# CANBUS_USB.net
KiCad netlist of a schematic drawn in EAGLE
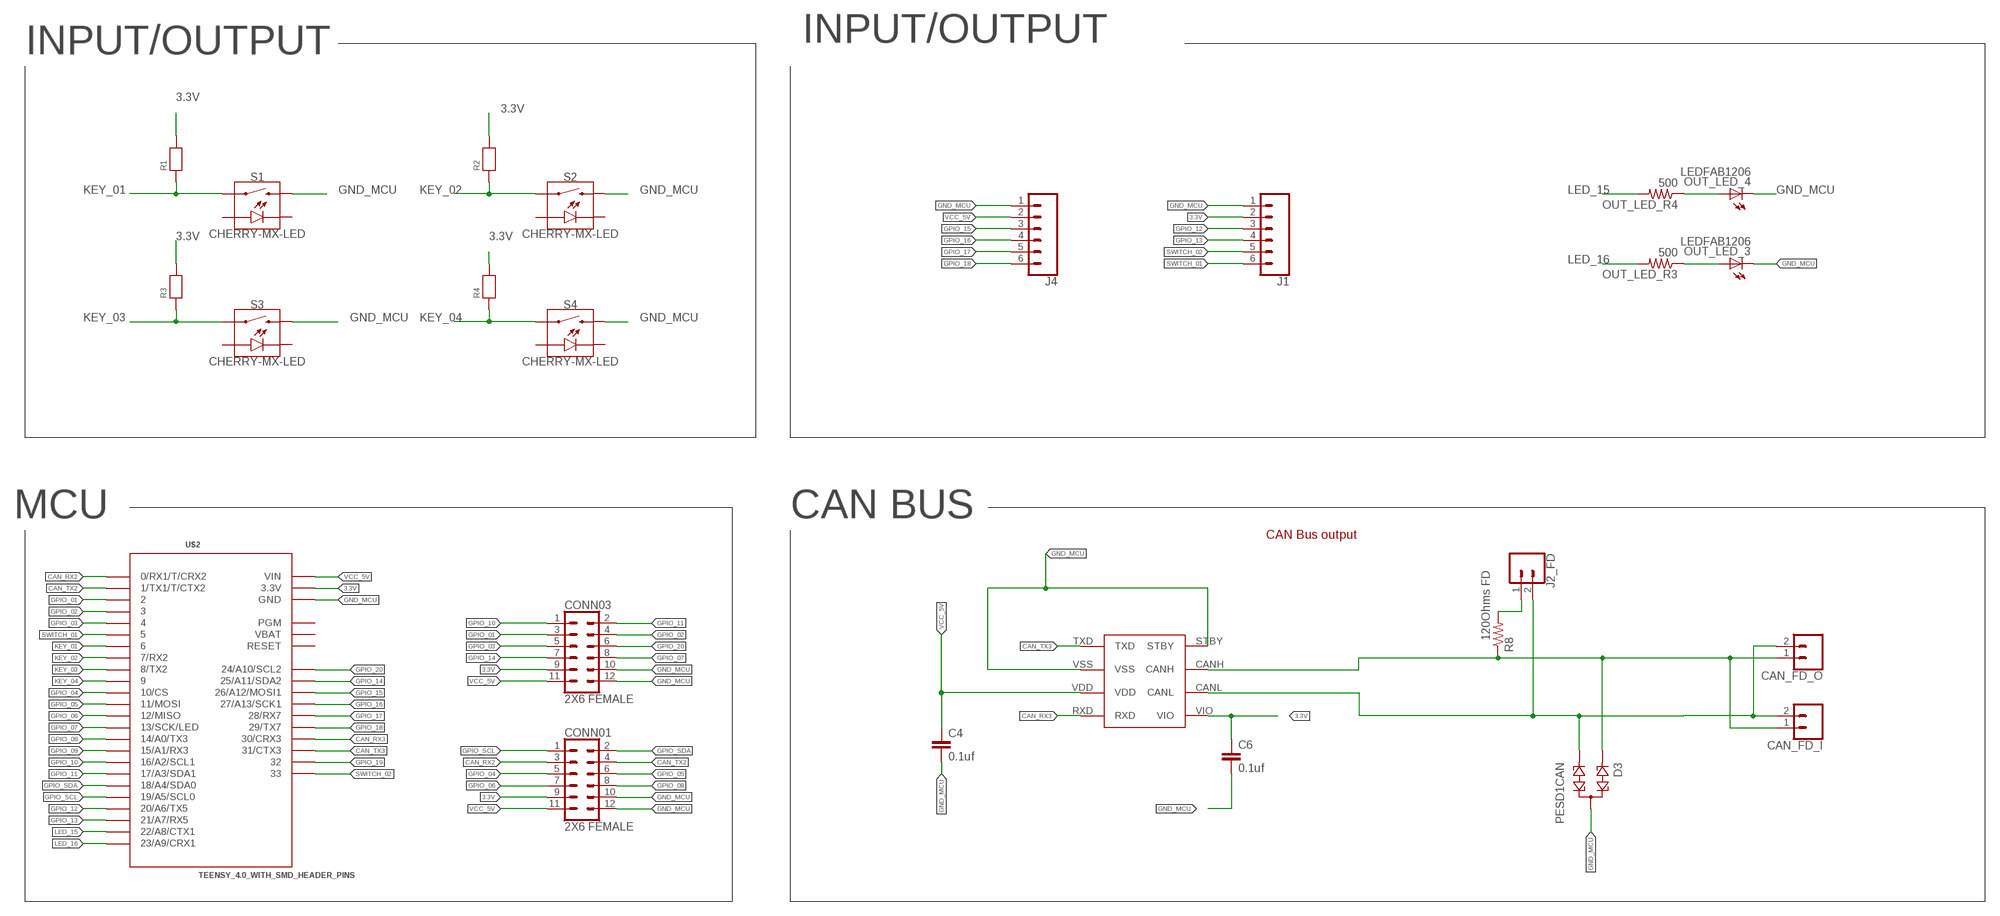
[diagram p0: schematic, sheet 1, part 1 of 2]
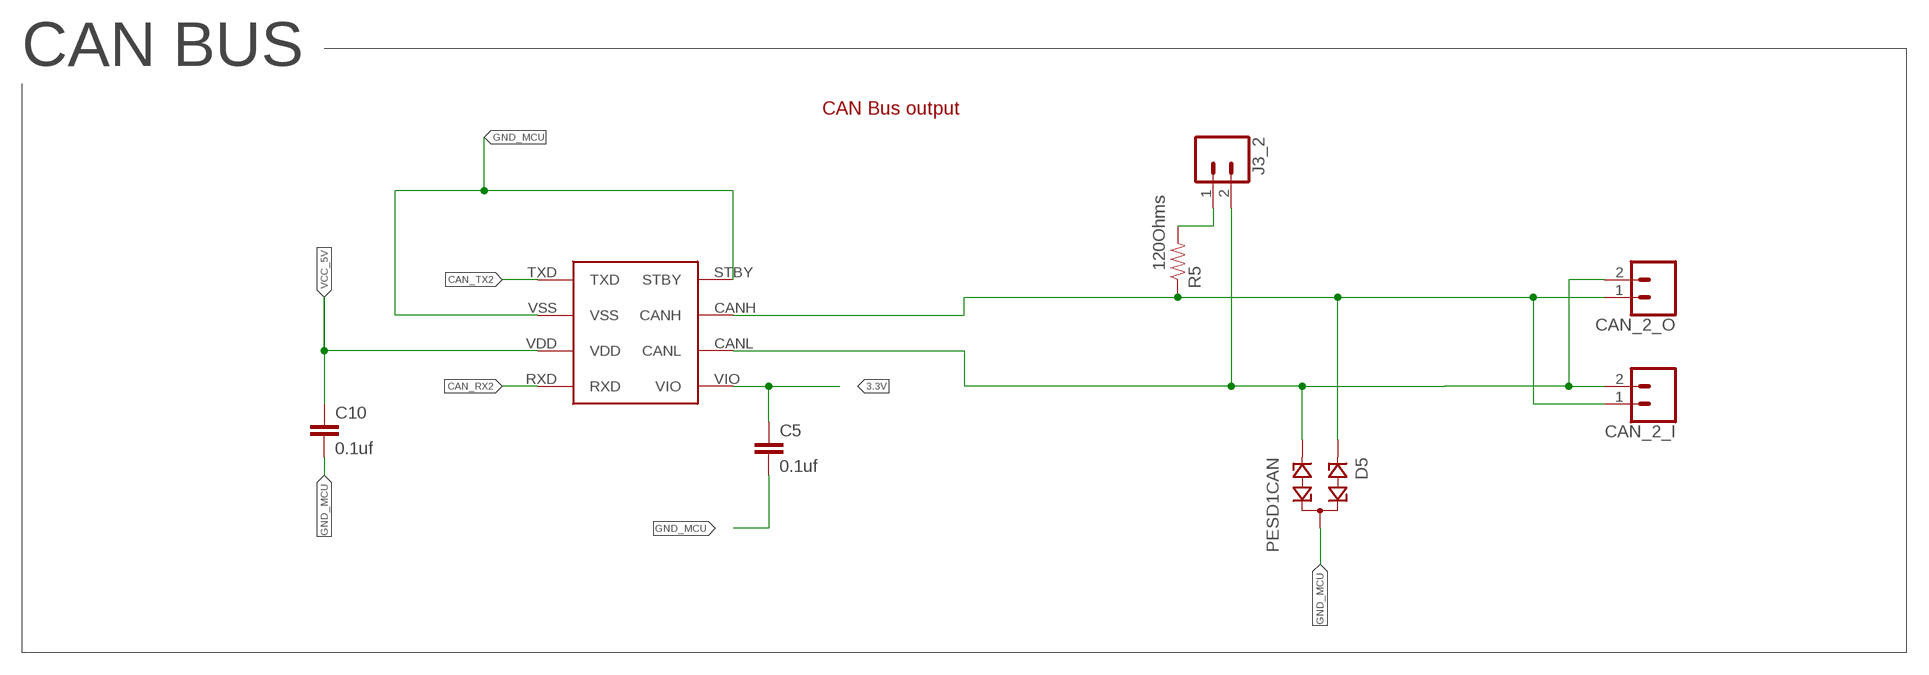
[diagram p1: schematic, sheet 1, part 2 of 2]

(export (version "E")
  (design (tool "Eeschema 10.0.6"))
  (components
    (comp (ref "C4")
      (value "0.1uf")
      (footprint "eagle-import:0603-CAP")
      (libsource (lib "eagle-import") (part "0.1UF-25V(+80/-20%)(0603)"))
    )
    (comp (ref "C5")
      (value "0.1uf")
      (footprint "eagle-import:0603-CAP")
      (libsource (lib "eagle-import") (part "0.1UF-25V(+80/-20%)(0603)"))
    )
    (comp (ref "C6")
      (value "0.1uf")
      (footprint "eagle-import:0603-CAP")
      (libsource (lib "eagle-import") (part "0.1UF-25V(+80/-20%)(0603)"))
    )
    (comp (ref "C10")
      (value "0.1uf")
      (footprint "eagle-import:0603-CAP")
      (libsource (lib "eagle-import") (part "0.1UF-25V(+80/-20%)(0603)"))
    )
    (comp (ref "CAN_2_I")
      (value "CONN_02-JST-2MM-SMT")
      (footprint "eagle-import:JST-2-SMD")
      (libsource (lib "eagle-import") (part "CONN_02-JST-2MM-SMT"))
    )
    (comp (ref "CAN_2_O")
      (value "CONN_02-JST-2MM-SMT")
      (footprint "eagle-import:JST-2-SMD")
      (libsource (lib "eagle-import") (part "CONN_02-JST-2MM-SMT"))
    )
    (comp (ref "CAN_FD_I")
      (value "CONN_02-JST-2MM-SMT")
      (footprint "eagle-import:JST-2-SMD")
      (libsource (lib "eagle-import") (part "CONN_02-JST-2MM-SMT"))
    )
    (comp (ref "CAN_FD_O")
      (value "CONN_02-JST-2MM-SMT")
      (footprint "eagle-import:JST-2-SMD")
      (libsource (lib "eagle-import") (part "CONN_02-JST-2MM-SMT"))
    )
    (comp (ref "CONN01")
      (value "2X6 FEMALE")
      (footprint "eagle-import:2X6")
      (libsource (lib "eagle-import") (part "CONN_06X2PTH_FEMALE"))
    )
    (comp (ref "CONN03")
      (value "2X6 FEMALE")
      (footprint "eagle-import:2X6")
      (libsource (lib "eagle-import") (part "CONN_06X2PTH_FEMALE"))
    )
    (comp (ref "D3")
      (value "PESD1CAN")
      (footprint "eagle-import:SOT23")
      (libsource (lib "eagle-import") (part "PESD1CAN"))
    )
    (comp (ref "D5")
      (value "PESD1CAN")
      (footprint "eagle-import:SOT23")
      (libsource (lib "eagle-import") (part "PESD1CAN"))
    )
    (comp (ref "J1")
      (value "CONN_06SMD-1MM")
      (footprint "eagle-import:1X06-1MM")
      (libsource (lib "eagle-import") (part "CONN_06SMD-1MM"))
    )
    (comp (ref "J2_FD")
      (value "CONN_02")
      (footprint "eagle-import:1X02")
      (libsource (lib "eagle-import") (part "CONN_02"))
    )
    (comp (ref "J3_2")
      (value "CONN_02")
      (footprint "eagle-import:1X02")
      (libsource (lib "eagle-import") (part "CONN_02"))
    )
    (comp (ref "J4")
      (value "CONN_06SMD-1MM")
      (footprint "eagle-import:1X06-1MM")
      (libsource (lib "eagle-import") (part "CONN_06SMD-1MM"))
    )
    (comp (ref "MCP2562")
      (value "MCP2562")
      (footprint "eagle-import:MCP2562")
      (libsource (lib "eagle-import") (part "MCP2562"))
    )
    (comp (ref "MCP2562FD")
      (value "MCP2562")
      (footprint "eagle-import:MCP2562")
      (libsource (lib "eagle-import") (part "MCP2562"))
    )
    (comp (ref "OUT_LED_3")
      (value "LEDFAB1206")
      (footprint "eagle-import:LED1206FAB")
      (libsource (lib "eagle-import") (part "LEDFAB1206"))
    )
    (comp (ref "OUT_LED_4")
      (value "LEDFAB1206")
      (footprint "eagle-import:LED1206FAB")
      (libsource (lib "eagle-import") (part "LEDFAB1206"))
    )
    (comp (ref "OUT_LED_R3")
      (value "500")
      (footprint "eagle-import:R1206FAB")
      (libsource (lib "eagle-import") (part "RES-US1206FAB"))
    )
    (comp (ref "OUT_LED_R4")
      (value "500")
      (footprint "eagle-import:R1206FAB")
      (libsource (lib "eagle-import") (part "RES-US1206FAB"))
    )
    (comp (ref "R1")
      (value "RESISTOR1206")
      (footprint "eagle-import:1206")
      (libsource (lib "eagle-import") (part "RESISTOR1206"))
    )
    (comp (ref "R2")
      (value "RESISTOR1206")
      (footprint "eagle-import:1206")
      (libsource (lib "eagle-import") (part "RESISTOR1206"))
    )
    (comp (ref "R3")
      (value "RESISTOR1206")
      (footprint "eagle-import:1206")
      (libsource (lib "eagle-import") (part "RESISTOR1206"))
    )
    (comp (ref "R4")
      (value "RESISTOR1206")
      (footprint "eagle-import:1206")
      (libsource (lib "eagle-import") (part "RESISTOR1206"))
    )
    (comp (ref "R5")
      (value "120Ohms")
      (footprint "eagle-import:0603-RES")
      (libsource (lib "eagle-import") (part "10KOHM-1/10W-1%(0603)0603"))
    )
    (comp (ref "R8")
      (value "120Ohms FD")
      (footprint "eagle-import:0603-RES")
      (libsource (lib "eagle-import") (part "10KOHM-1/10W-1%(0603)0603"))
    )
    (comp (ref "S1")
      (value "CHERRY-MX-LED")
      (footprint "eagle-import:CHERRY-MX-LED")
      (libsource (lib "eagle-import") (part "CHERRY-MX-LED"))
    )
    (comp (ref "S2")
      (value "CHERRY-MX-LED")
      (footprint "eagle-import:CHERRY-MX-LED")
      (libsource (lib "eagle-import") (part "CHERRY-MX-LED"))
    )
    (comp (ref "S3")
      (value "CHERRY-MX-LED")
      (footprint "eagle-import:CHERRY-MX-LED")
      (libsource (lib "eagle-import") (part "CHERRY-MX-LED"))
    )
    (comp (ref "S4")
      (value "CHERRY-MX-LED")
      (footprint "eagle-import:CHERRY-MX-LED")
      (libsource (lib "eagle-import") (part "CHERRY-MX-LED"))
    )
    (comp (ref "U$2")
      (value "TEENSY_4.0_WITH_SMD_HEADER_PINS")
      (footprint "eagle-import:TEENSY_4.0_WITH_SMD_HEADER_PINS")
      (libsource (lib "eagle-import") (part "TEENSY_4.0_WITH_SMD_HEADER_PINS"))
    )
  )
  (nets
    (net (code "1") (name "/VBAT") (class "Default")
      (node (ref "U$2") (pin "VBAT") (pinfunction "VBAT_VBAT") (pintype "power_in"))
    )
    (net (code "2") (name "3.3V") (class "Default")
      (node (ref "C5") (pin "1") (pinfunction "1_1") (pintype "passive"))
      (node (ref "C6") (pin "1") (pinfunction "1_1") (pintype "passive"))
      (node (ref "CONN01") (pin "9") (pinfunction "9_9") (pintype "passive"))
      (node (ref "CONN03") (pin "9") (pinfunction "9_9") (pintype "passive"))
      (node (ref "J1") (pin "2") (pinfunction "2_2") (pintype "passive"))
      (node (ref "MCP2562") (pin "VIO") (pinfunction "VIO_VIO") (pintype "bidirectional"))
      (node (ref "MCP2562FD") (pin "VIO") (pinfunction "VIO_VIO") (pintype "bidirectional"))
      (node (ref "R1") (pin "2") (pinfunction "2_2") (pintype "passive"))
      (node (ref "R2") (pin "2") (pinfunction "2_2") (pintype "passive"))
      (node (ref "R3") (pin "2") (pinfunction "2_2") (pintype "passive"))
      (node (ref "R4") (pin "2") (pinfunction "2_2") (pintype "passive"))
      (node (ref "U$2") (pin "3.3V") (pinfunction "3.3V_3.3V") (pintype "power_in"))
      (node (ref "U$2") (pin "3.3V1") (pinfunction "3.3V_3.3V1") (pintype "power_in"))
    )
    (net (code "3") (name "CAN_RX2") (class "Default")
      (node (ref "CONN01") (pin "3") (pinfunction "3_3") (pintype "passive"))
      (node (ref "MCP2562") (pin "RXD") (pinfunction "RXD_RXD") (pintype "bidirectional"))
      (node (ref "U$2") (pin "0") (pinfunction "0/RX1/T/CRX2_0") (pintype "bidirectional"))
    )
    (net (code "4") (name "CAN_RX3") (class "Default")
      (node (ref "MCP2562FD") (pin "RXD") (pinfunction "RXD_RXD") (pintype "bidirectional"))
      (node (ref "U$2") (pin "30") (pinfunction "30/CRX3_30") (pintype "bidirectional"))
    )
    (net (code "5") (name "CAN_TX2") (class "Default")
      (node (ref "CONN01") (pin "4") (pinfunction "4_4") (pintype "passive"))
      (node (ref "MCP2562") (pin "TXD") (pinfunction "TXD_TXD") (pintype "bidirectional"))
      (node (ref "U$2") (pin "1") (pinfunction "1/TX1/T/CTX2_1") (pintype "bidirectional"))
    )
    (net (code "6") (name "CAN_TX3") (class "Default")
      (node (ref "MCP2562FD") (pin "TXD") (pinfunction "TXD_TXD") (pintype "bidirectional"))
      (node (ref "U$2") (pin "31") (pinfunction "31/CTX3_31") (pintype "bidirectional"))
    )
    (net (code "7") (name "GND_MCU") (class "Default")
      (node (ref "C10") (pin "2") (pinfunction "2_2") (pintype "passive"))
      (node (ref "C4") (pin "2") (pinfunction "2_2") (pintype "passive"))
      (node (ref "C5") (pin "2") (pinfunction "2_2") (pintype "passive"))
      (node (ref "C6") (pin "2") (pinfunction "2_2") (pintype "passive"))
      (node (ref "CONN01") (pin "10") (pinfunction "10_10") (pintype "passive"))
      (node (ref "CONN01") (pin "12") (pinfunction "12_12") (pintype "passive"))
      (node (ref "CONN03") (pin "10") (pinfunction "10_10") (pintype "passive"))
      (node (ref "CONN03") (pin "12") (pinfunction "12_12") (pintype "passive"))
      (node (ref "D3") (pin "3") (pinfunction "3_3") (pintype "passive"))
      (node (ref "D5") (pin "3") (pinfunction "3_3") (pintype "passive"))
      (node (ref "J1") (pin "1") (pinfunction "1_1") (pintype "passive"))
      (node (ref "J4") (pin "1") (pinfunction "1_1") (pintype "passive"))
      (node (ref "MCP2562") (pin "STBY") (pinfunction "STBY_STBY") (pintype "bidirectional"))
      (node (ref "MCP2562") (pin "VSS") (pinfunction "VSS_VSS") (pintype "bidirectional"))
      (node (ref "MCP2562FD") (pin "STBY") (pinfunction "STBY_STBY") (pintype "bidirectional"))
      (node (ref "MCP2562FD") (pin "VSS") (pinfunction "VSS_VSS") (pintype "bidirectional"))
      (node (ref "OUT_LED_3") (pin "2") (pinfunction "C_2") (pintype "passive"))
      (node (ref "OUT_LED_4") (pin "2") (pinfunction "C_2") (pintype "passive"))
      (node (ref "S1") (pin "S2") (pinfunction "S2_S2") (pintype "passive"))
      (node (ref "S2") (pin "S2") (pinfunction "S2_S2") (pintype "passive"))
      (node (ref "S3") (pin "S2") (pinfunction "S2_S2") (pintype "passive"))
      (node (ref "S4") (pin "S2") (pinfunction "S2_S2") (pintype "passive"))
      (node (ref "U$2") (pin "GND") (pinfunction "GND_GND") (pintype "power_in"))
      (node (ref "U$2") (pin "GND1") (pinfunction "GND_GND1") (pintype "power_in"))
      (node (ref "U$2") (pin "GND2") (pinfunction "GND_GND2") (pintype "power_in"))
    )
    (net (code "8") (name "GPIO_01") (class "Default")
      (node (ref "CONN03") (pin "3") (pinfunction "3_3") (pintype "passive"))
      (node (ref "U$2") (pin "2") (pinfunction "2_2") (pintype "bidirectional"))
    )
    (net (code "9") (name "GPIO_02") (class "Default")
      (node (ref "CONN03") (pin "4") (pinfunction "4_4") (pintype "passive"))
      (node (ref "U$2") (pin "3") (pinfunction "3_3") (pintype "bidirectional"))
    )
    (net (code "10") (name "GPIO_03") (class "Default")
      (node (ref "CONN03") (pin "5") (pinfunction "5_5") (pintype "passive"))
      (node (ref "U$2") (pin "4") (pinfunction "4_4") (pintype "bidirectional"))
    )
    (net (code "11") (name "GPIO_04") (class "Default")
      (node (ref "CONN01") (pin "5") (pinfunction "5_5") (pintype "passive"))
      (node (ref "U$2") (pin "10") (pinfunction "10/CS_10") (pintype "bidirectional"))
    )
    (net (code "12") (name "GPIO_05") (class "Default")
      (node (ref "CONN01") (pin "6") (pinfunction "6_6") (pintype "passive"))
      (node (ref "U$2") (pin "11") (pinfunction "11/MOSI_11") (pintype "bidirectional"))
    )
    (net (code "13") (name "GPIO_06") (class "Default")
      (node (ref "CONN01") (pin "7") (pinfunction "7_7") (pintype "passive"))
      (node (ref "U$2") (pin "12") (pinfunction "12/MISO_12") (pintype "bidirectional"))
    )
    (net (code "14") (name "GPIO_07") (class "Default")
      (node (ref "CONN03") (pin "8") (pinfunction "8_8") (pintype "passive"))
      (node (ref "U$2") (pin "13") (pinfunction "13/SCK/LED_13") (pintype "bidirectional"))
    )
    (net (code "15") (name "GPIO_08") (class "Default")
      (node (ref "CONN01") (pin "8") (pinfunction "8_8") (pintype "passive"))
      (node (ref "U$2") (pin "14/A0") (pinfunction "14/A0/TX3_14/A0") (pintype "bidirectional"))
    )
    (net (code "16") (name "GPIO_09") (class "Default")
      (node (ref "U$2") (pin "15/A1") (pinfunction "15/A1/RX3_15/A1") (pintype "bidirectional"))
    )
    (net (code "17") (name "GPIO_10") (class "Default")
      (node (ref "CONN03") (pin "1") (pinfunction "1_1") (pintype "passive"))
      (node (ref "U$2") (pin "16/A2") (pinfunction "16/A2/SCL1_16/A2") (pintype "bidirectional"))
    )
    (net (code "18") (name "GPIO_11") (class "Default")
      (node (ref "CONN03") (pin "2") (pinfunction "2_2") (pintype "passive"))
      (node (ref "U$2") (pin "17/A3") (pinfunction "17/A3/SDA1_17/A3") (pintype "bidirectional"))
    )
    (net (code "19") (name "GPIO_12") (class "Default")
      (node (ref "J1") (pin "3") (pinfunction "3_3") (pintype "passive"))
      (node (ref "U$2") (pin "20/A6") (pinfunction "20/A6/TX5_20/A6") (pintype "bidirectional"))
    )
    (net (code "20") (name "GPIO_13") (class "Default")
      (node (ref "J1") (pin "4") (pinfunction "4_4") (pintype "passive"))
      (node (ref "U$2") (pin "21/A7") (pinfunction "21/A7/RX5_21/A7") (pintype "bidirectional"))
    )
    (net (code "21") (name "GPIO_14") (class "Default")
      (node (ref "CONN03") (pin "7") (pinfunction "7_7") (pintype "passive"))
      (node (ref "U$2") (pin "25") (pinfunction "25/A11/SDA2_25") (pintype "bidirectional"))
    )
    (net (code "22") (name "GPIO_15") (class "Default")
      (node (ref "J4") (pin "3") (pinfunction "3_3") (pintype "passive"))
      (node (ref "U$2") (pin "26") (pinfunction "26/A12/MOSI1_26") (pintype "bidirectional"))
    )
    (net (code "23") (name "GPIO_16") (class "Default")
      (node (ref "J4") (pin "4") (pinfunction "4_4") (pintype "passive"))
      (node (ref "U$2") (pin "27") (pinfunction "27/A13/SCK1_27") (pintype "bidirectional"))
    )
    (net (code "24") (name "GPIO_17") (class "Default")
      (node (ref "J4") (pin "5") (pinfunction "5_5") (pintype "passive"))
      (node (ref "U$2") (pin "28") (pinfunction "28/RX7_28") (pintype "bidirectional"))
    )
    (net (code "25") (name "GPIO_18") (class "Default")
      (node (ref "J4") (pin "6") (pinfunction "6_6") (pintype "passive"))
      (node (ref "U$2") (pin "29") (pinfunction "29/TX7_29") (pintype "bidirectional"))
    )
    (net (code "26") (name "GPIO_19") (class "Default")
      (node (ref "U$2") (pin "32") (pinfunction "32_32") (pintype "bidirectional"))
    )
    (net (code "27") (name "GPIO_20") (class "Default")
      (node (ref "CONN03") (pin "6") (pinfunction "6_6") (pintype "passive"))
      (node (ref "U$2") (pin "24") (pinfunction "24/A10/SCL2_24") (pintype "bidirectional"))
    )
    (net (code "28") (name "GPIO_SCL") (class "Default")
      (node (ref "CONN01") (pin "1") (pinfunction "1_1") (pintype "passive"))
      (node (ref "U$2") (pin "19/A5") (pinfunction "19/A5/SCL0_19/A5") (pintype "bidirectional"))
    )
    (net (code "29") (name "GPIO_SDA") (class "Default")
      (node (ref "CONN01") (pin "2") (pinfunction "2_2") (pintype "passive"))
      (node (ref "U$2") (pin "18/A4") (pinfunction "18/A4/SDA0_18/A4") (pintype "bidirectional"))
    )
    (net (code "30") (name "KEY_01") (class "Default")
      (node (ref "R1") (pin "1") (pinfunction "1_1") (pintype "passive"))
      (node (ref "S1") (pin "S1") (pinfunction "S1_S1") (pintype "passive"))
      (node (ref "U$2") (pin "6") (pinfunction "6_6") (pintype "bidirectional"))
    )
    (net (code "31") (name "KEY_02") (class "Default")
      (node (ref "R2") (pin "1") (pinfunction "1_1") (pintype "passive"))
      (node (ref "S2") (pin "S1") (pinfunction "S1_S1") (pintype "passive"))
      (node (ref "U$2") (pin "7") (pinfunction "7/RX2_7") (pintype "bidirectional"))
    )
    (net (code "32") (name "KEY_03") (class "Default")
      (node (ref "R3") (pin "1") (pinfunction "1_1") (pintype "passive"))
      (node (ref "S3") (pin "S1") (pinfunction "S1_S1") (pintype "passive"))
      (node (ref "U$2") (pin "8") (pinfunction "8/TX2_8") (pintype "bidirectional"))
    )
    (net (code "33") (name "KEY_04") (class "Default")
      (node (ref "R4") (pin "1") (pinfunction "1_1") (pintype "passive"))
      (node (ref "S4") (pin "S1") (pinfunction "S1_S1") (pintype "passive"))
      (node (ref "U$2") (pin "9") (pinfunction "9_9") (pintype "bidirectional"))
    )
    (net (code "34") (name "LED_15") (class "Default")
      (node (ref "OUT_LED_R4") (pin "2") (pinfunction "2_2") (pintype "passive"))
      (node (ref "U$2") (pin "22/A8") (pinfunction "22/A8/CTX1_22/A8") (pintype "bidirectional"))
    )
    (net (code "35") (name "LED_16") (class "Default")
      (node (ref "OUT_LED_R3") (pin "2") (pinfunction "2_2") (pintype "passive"))
      (node (ref "U$2") (pin "23/A9") (pinfunction "23/A9/CRX1_23/A9") (pintype "bidirectional"))
    )
    (net (code "36") (name "Net-(CAN_2_I-1)") (class "Default")
      (node (ref "CAN_2_I") (pin "2") (pinfunction "1_2") (pintype "passive"))
      (node (ref "CAN_2_O") (pin "2") (pinfunction "1_2") (pintype "passive"))
      (node (ref "D5") (pin "2") (pinfunction "2_2") (pintype "passive"))
      (node (ref "J3_2") (pin "2") (pinfunction "2_2") (pintype "passive"))
      (node (ref "MCP2562") (pin "CANL") (pinfunction "CANL_CANL") (pintype "bidirectional"))
    )
    (net (code "37") (name "Net-(CAN_2_I-2)") (class "Default")
      (node (ref "CAN_2_I") (pin "1") (pinfunction "2_1") (pintype "passive"))
      (node (ref "CAN_2_O") (pin "1") (pinfunction "2_1") (pintype "passive"))
      (node (ref "D5") (pin "1") (pinfunction "1_1") (pintype "passive"))
      (node (ref "MCP2562") (pin "CANH") (pinfunction "CANH_CANH") (pintype "bidirectional"))
      (node (ref "R5") (pin "1") (pinfunction "1_1") (pintype "passive"))
    )
    (net (code "38") (name "Net-(CAN_FD_I-1)") (class "Default")
      (node (ref "CAN_FD_I") (pin "2") (pinfunction "1_2") (pintype "passive"))
      (node (ref "CAN_FD_O") (pin "2") (pinfunction "1_2") (pintype "passive"))
      (node (ref "D3") (pin "2") (pinfunction "2_2") (pintype "passive"))
      (node (ref "J2_FD") (pin "2") (pinfunction "2_2") (pintype "passive"))
      (node (ref "MCP2562FD") (pin "CANL") (pinfunction "CANL_CANL") (pintype "bidirectional"))
    )
    (net (code "39") (name "Net-(CAN_FD_I-2)") (class "Default")
      (node (ref "CAN_FD_I") (pin "1") (pinfunction "2_1") (pintype "passive"))
      (node (ref "CAN_FD_O") (pin "1") (pinfunction "2_1") (pintype "passive"))
      (node (ref "D3") (pin "1") (pinfunction "1_1") (pintype "passive"))
      (node (ref "MCP2562FD") (pin "CANH") (pinfunction "CANH_CANH") (pintype "bidirectional"))
      (node (ref "R8") (pin "1") (pinfunction "1_1") (pintype "passive"))
    )
    (net (code "40") (name "Net-(J2_FD-Pad1)") (class "Default")
      (node (ref "J2_FD") (pin "1") (pinfunction "1_1") (pintype "passive"))
      (node (ref "R8") (pin "2") (pinfunction "2_2") (pintype "passive"))
    )
    (net (code "41") (name "Net-(J3_2-Pad1)") (class "Default")
      (node (ref "J3_2") (pin "1") (pinfunction "1_1") (pintype "passive"))
      (node (ref "R5") (pin "2") (pinfunction "2_2") (pintype "passive"))
    )
    (net (code "42") (name "Net-(OUT_LED_3-A)") (class "Default")
      (node (ref "OUT_LED_3") (pin "1") (pinfunction "A_1") (pintype "passive"))
      (node (ref "OUT_LED_R3") (pin "1") (pinfunction "1_1") (pintype "passive"))
    )
    (net (code "43") (name "Net-(OUT_LED_4-A)") (class "Default")
      (node (ref "OUT_LED_4") (pin "1") (pinfunction "A_1") (pintype "passive"))
      (node (ref "OUT_LED_R4") (pin "1") (pinfunction "1_1") (pintype "passive"))
    )
    (net (code "44") (name "SWITCH_01") (class "Default")
      (node (ref "J1") (pin "6") (pinfunction "6_6") (pintype "passive"))
      (node (ref "U$2") (pin "5") (pinfunction "5_5") (pintype "bidirectional"))
    )
    (net (code "45") (name "SWITCH_02") (class "Default")
      (node (ref "J1") (pin "5") (pinfunction "5_5") (pintype "passive"))
      (node (ref "U$2") (pin "33") (pinfunction "33_33") (pintype "bidirectional"))
    )
    (net (code "46") (name "VCC_5V") (class "Default")
      (node (ref "C10") (pin "1") (pinfunction "1_1") (pintype "passive"))
      (node (ref "C4") (pin "1") (pinfunction "1_1") (pintype "passive"))
      (node (ref "CONN01") (pin "11") (pinfunction "11_11") (pintype "passive"))
      (node (ref "CONN03") (pin "11") (pinfunction "11_11") (pintype "passive"))
      (node (ref "J4") (pin "2") (pinfunction "2_2") (pintype "passive"))
      (node (ref "MCP2562") (pin "VDD") (pinfunction "VDD_VDD") (pintype "bidirectional"))
      (node (ref "MCP2562FD") (pin "VDD") (pinfunction "VDD_VDD") (pintype "bidirectional"))
      (node (ref "U$2") (pin "VIN") (pinfunction "VIN_VIN") (pintype "power_in"))
    )
    (net (code "47") (name "unconnected-(S1-C-PadK)") (class "Default")
      (node (ref "S1") (pin "K") (pinfunction "C_K") (pintype "passive"))
    )
    (net (code "48") (name "unconnected-(S1-PadA)") (class "Default")
      (node (ref "S1") (pin "A") (pinfunction "A_A") (pintype "passive"))
    )
    (net (code "49") (name "unconnected-(S2-C-PadK)") (class "Default")
      (node (ref "S2") (pin "K") (pinfunction "C_K") (pintype "passive"))
    )
    (net (code "50") (name "unconnected-(S2-PadA)") (class "Default")
      (node (ref "S2") (pin "A") (pinfunction "A_A") (pintype "passive"))
    )
    (net (code "51") (name "unconnected-(S3-C-PadK)") (class "Default")
      (node (ref "S3") (pin "K") (pinfunction "C_K") (pintype "passive"))
    )
    (net (code "52") (name "unconnected-(S3-PadA)") (class "Default")
      (node (ref "S3") (pin "A") (pinfunction "A_A") (pintype "passive"))
    )
    (net (code "53") (name "unconnected-(S4-C-PadK)") (class "Default")
      (node (ref "S4") (pin "K") (pinfunction "C_K") (pintype "passive"))
    )
    (net (code "54") (name "unconnected-(S4-PadA)") (class "Default")
      (node (ref "S4") (pin "A") (pinfunction "A_A") (pintype "passive"))
    )
    (net (code "55") (name "unconnected-(U$2-PadPGM)") (class "Default")
      (node (ref "U$2") (pin "PGM") (pinfunction "PGM_PGM") (pintype "bidirectional"))
    )
    (net (code "56") (name "unconnected-(U$2-PadRESET)") (class "Default")
      (node (ref "U$2") (pin "RESET") (pinfunction "RESET_RESET") (pintype "bidirectional"))
    )
  )
)
